# mcu.net
KiCad netlist of a schematic drawn in Altium Designer
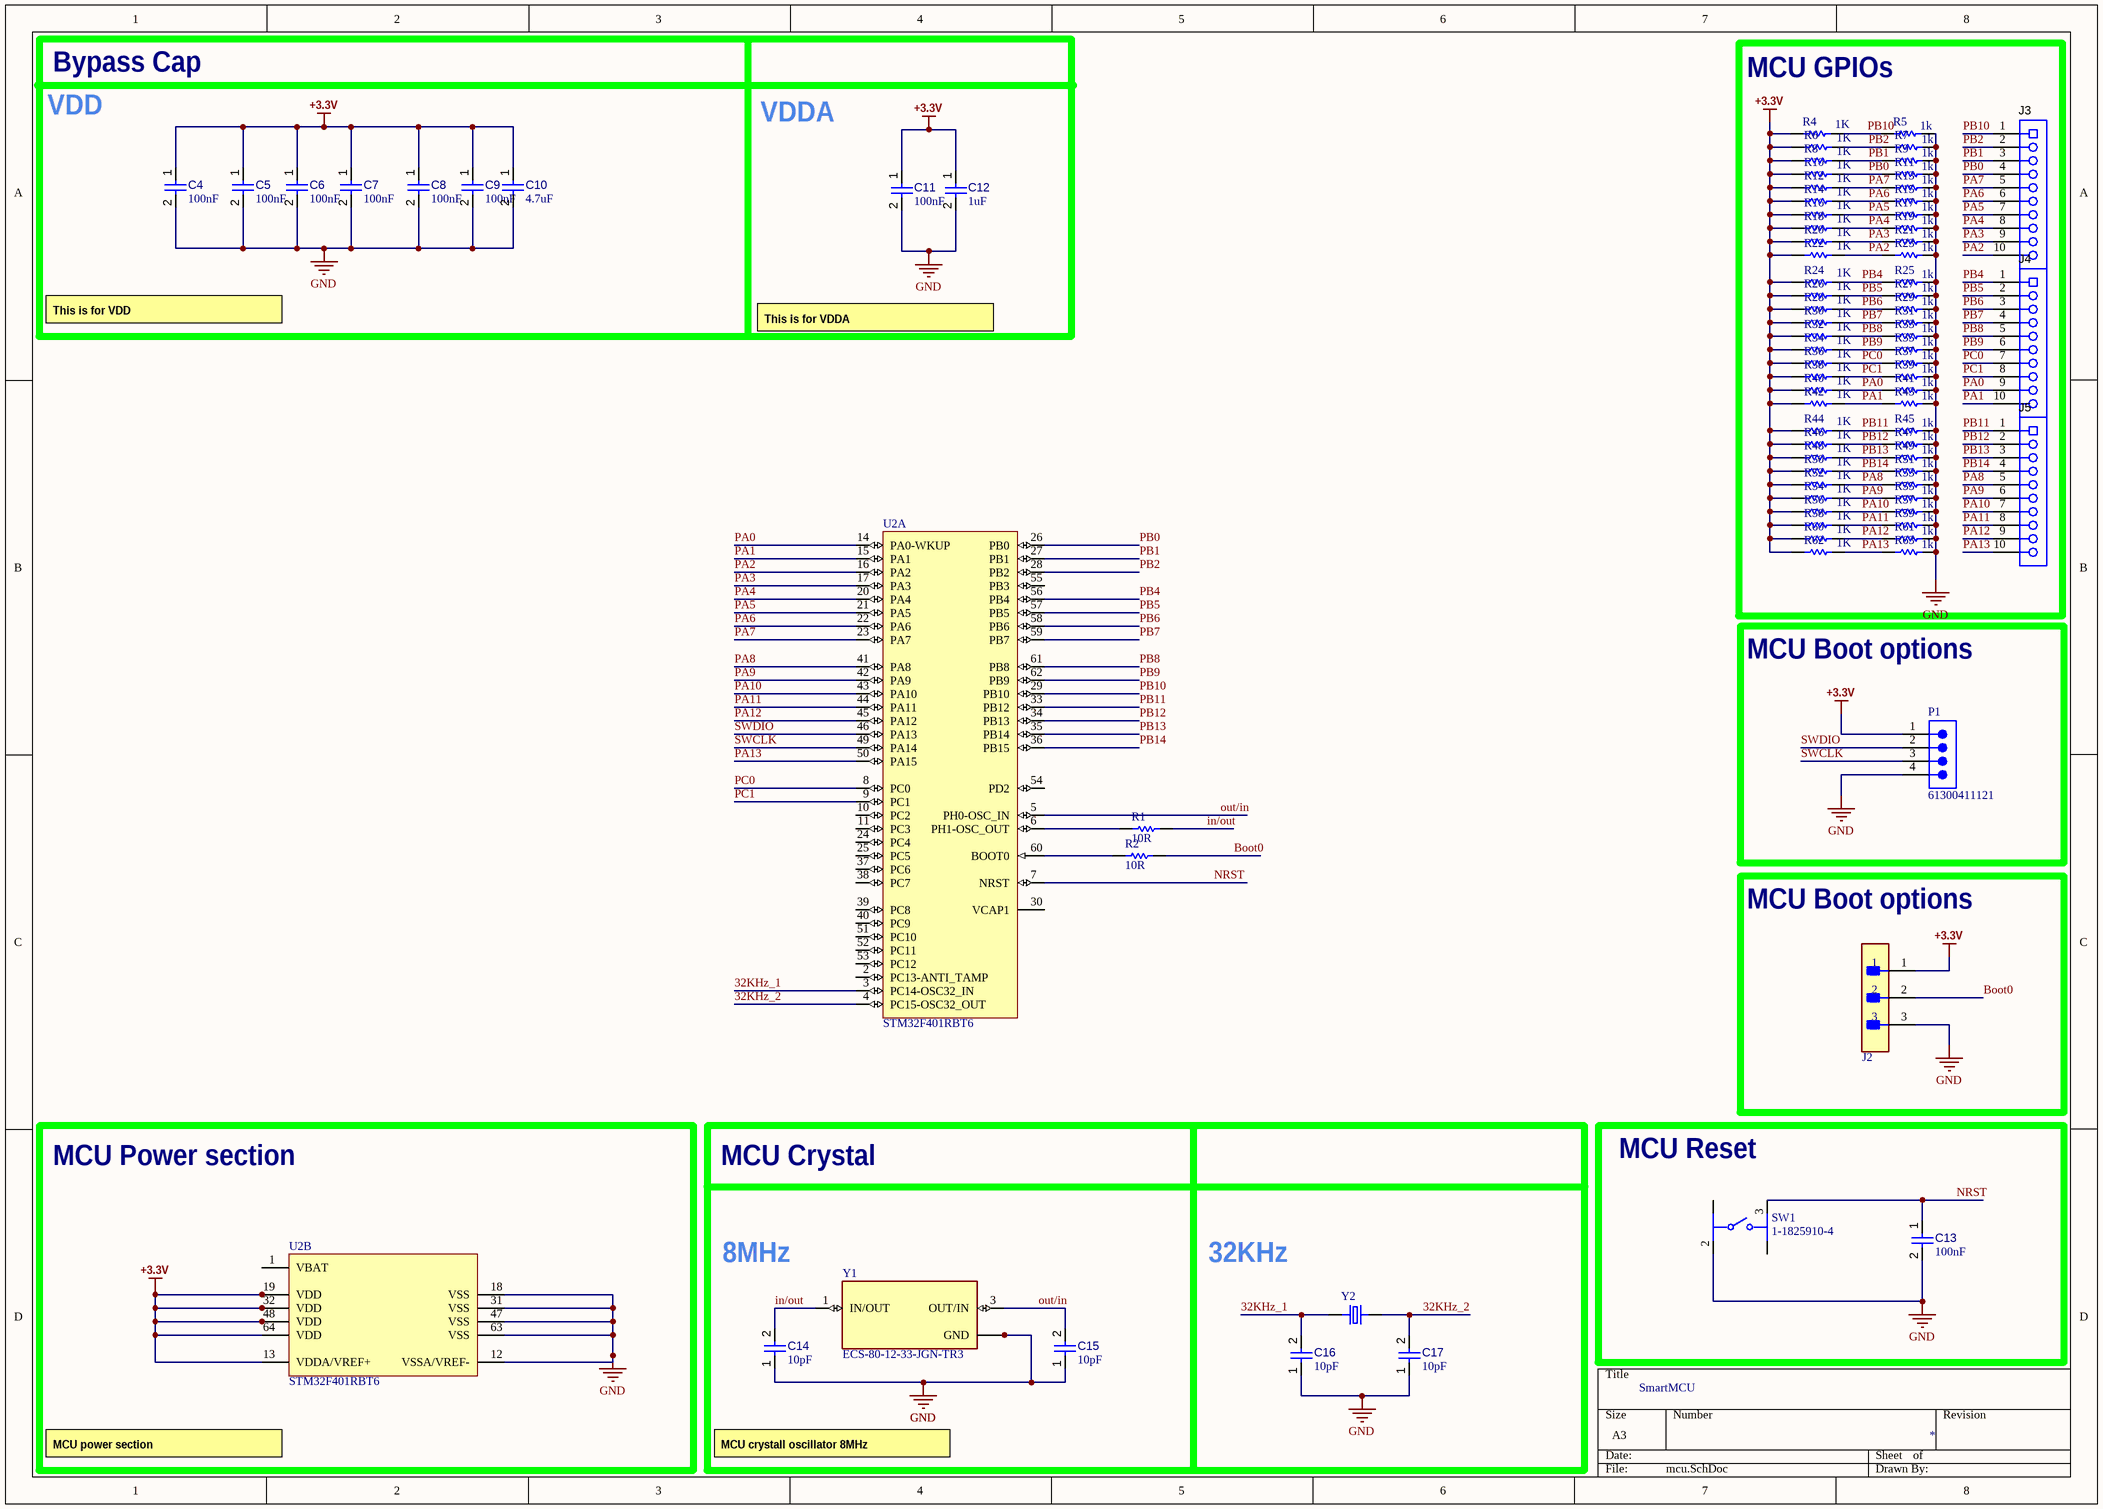
[diagram p0: mcu.SchDoc]

(export (version "E")
  (design (tool "Eeschema 10.0.6"))
  (components
    (comp (ref "C4")
      (value "100nF")
      (footprint "CAPC0603(1608)100_L")
      (description "Chip Capacitor, 4.7µF +/-20%, 10V, 0603, Thickness 1 mm")
      (fields (field (name "TOLERANCE") "10%") (field (name "Comment") "Capacitor 4.7µF +/-20% 10V 0603"))
      (libsource (lib "Altium Cloud") (part "CAP-NP-2"))
    )
    (comp (ref "C5")
      (value "100nF")
      (footprint "CAPC0603(1608)100_L")
      (description "Chip Capacitor, 4.7µF +/-20%, 10V, 0603, Thickness 1 mm")
      (fields (field (name "TOLERANCE") "10%") (field (name "Comment") "Capacitor 4.7µF +/-20% 10V 0603"))
      (libsource (lib "Altium Cloud") (part "CAP-NP-2"))
    )
    (comp (ref "C6")
      (value "100nF")
      (footprint "CAPC0603(1608)100_L")
      (description "Chip Capacitor, 4.7µF +/-20%, 10V, 0603, Thickness 1 mm")
      (fields (field (name "TOLERANCE") "10%") (field (name "Comment") "Capacitor 4.7µF +/-20% 10V 0603"))
      (libsource (lib "Altium Cloud") (part "CAP-NP-2"))
    )
    (comp (ref "C7")
      (value "100nF")
      (footprint "CAPC0603(1608)100_L")
      (description "Chip Capacitor, 4.7µF +/-20%, 10V, 0603, Thickness 1 mm")
      (fields (field (name "TOLERANCE") "10%") (field (name "Comment") "Capacitor 4.7µF +/-20% 10V 0603"))
      (libsource (lib "Altium Cloud") (part "CAP-NP-2"))
    )
    (comp (ref "C8")
      (value "100nF")
      (footprint "CAPC0603(1608)100_L")
      (description "Chip Capacitor, 4.7µF +/-20%, 10V, 0603, Thickness 1 mm")
      (fields (field (name "TOLERANCE") "10%") (field (name "Comment") "Capacitor 4.7µF +/-20% 10V 0603"))
      (libsource (lib "Altium Cloud") (part "CAP-NP-2"))
    )
    (comp (ref "C9")
      (value "100nF")
      (footprint "CAPC0603(1608)100_L")
      (description "Chip Capacitor, 4.7µF +/-20%, 10V, 0603, Thickness 1 mm")
      (fields (field (name "TOLERANCE") "10%") (field (name "Comment") "Capacitor 4.7µF +/-20% 10V 0603"))
      (libsource (lib "Altium Cloud") (part "CAP-NP-2"))
    )
    (comp (ref "C10")
      (value "4.7uF")
      (footprint "CAPC0603(1608)100_L")
      (description "Chip Capacitor, 4.7µF +/-20%, 10V, 0603, Thickness 1 mm")
      (fields (field (name "TOLERANCE") "10%") (field (name "Comment") "Capacitor 4.7µF +/-20% 10V 0603"))
      (libsource (lib "Altium Cloud") (part "CAP-NP-2"))
    )
    (comp (ref "C11")
      (value "100nF")
      (footprint "CAPC0603(1608)100_L")
      (description "Chip Capacitor, 4.7µF +/-20%, 10V, 0603, Thickness 1 mm")
      (fields (field (name "TOLERANCE") "10%") (field (name "Comment") "Capacitor 4.7µF +/-20% 10V 0603"))
      (libsource (lib "Altium Cloud") (part "CAP-NP-2"))
    )
    (comp (ref "C12")
      (value "1uF")
      (footprint "CAPC0603(1608)100_L")
      (description "Chip Capacitor, 4.7µF +/-20%, 10V, 0603, Thickness 1 mm")
      (fields (field (name "TOLERANCE") "10%") (field (name "Comment") "Capacitor 4.7µF +/-20% 10V 0603"))
      (libsource (lib "Altium Cloud") (part "CAP-NP-2"))
    )
    (comp (ref "C13")
      (value "100nF")
      (footprint "CAPC0603(1608)100_L")
      (description "Chip Capacitor, 4.7µF +/-20%, 10V, 0603, Thickness 1 mm")
      (fields (field (name "TOLERANCE") "10%") (field (name "Comment") "Capacitor 4.7µF +/-20% 10V 0603"))
      (libsource (lib "Altium Cloud") (part "CAP-NP-2"))
    )
    (comp (ref "C14")
      (value "10pF")
      (footprint "CAPC0402(1005)33_L")
      (description "Chip Capacitor, 12pF +/-10%, 50V, 0402, Thickness 0.33 mm")
      (fields (field (name "TOLERANCE") "20%") (field (name "Comment") "Capacitor 12pF +/-10% 50V 0402"))
      (libsource (lib "Altium Cloud") (part "CAP-NP-2"))
    )
    (comp (ref "C15")
      (value "10pF")
      (footprint "CAPC0402(1005)33_L")
      (description "Chip Capacitor, 12pF +/-10%, 50V, 0402, Thickness 0.33 mm")
      (fields (field (name "TOLERANCE") "20%") (field (name "Comment") "Capacitor 12pF +/-10% 50V 0402"))
      (libsource (lib "Altium Cloud") (part "CAP-NP-2"))
    )
    (comp (ref "C16")
      (value "10pF")
      (footprint "CAPC0402(1005)33_L")
      (description "Chip Capacitor, 12pF +/-10%, 50V, 0402, Thickness 0.33 mm")
      (fields (field (name "TOLERANCE") "20%") (field (name "Comment") "Capacitor 12pF +/-10% 50V 0402"))
      (libsource (lib "Altium Cloud") (part "CAP-NP-2"))
    )
    (comp (ref "C17")
      (value "10pF")
      (footprint "CAPC0402(1005)33_L")
      (description "Chip Capacitor, 12pF +/-10%, 50V, 0402, Thickness 0.33 mm")
      (fields (field (name "TOLERANCE") "20%") (field (name "Comment") "Capacitor 12pF +/-10% 50V 0402"))
      (libsource (lib "Altium Cloud") (part "CAP-NP-2"))
    )
    (comp (ref "J2")
      (value "951103-8622-AR")
      (footprint "FP-951103-8622-AR-MFG")
      (description "CONN HEADER VERT 3POS 2MM")
      (fields
        (field (name "OCTOPART") "https://octopart.com/951103-8622-ar-3m-14400669")
        (field (name "MANUFACTURER") "3M")
      )
      (libsource (lib "Altium Content Vault") (part "0d3f023dd272f625e17a2be33dea85f"))
    )
    (comp (ref "J3")
      (value "5-534237-8")
      (footprint "TECO-5-534237-8_V")
      (fields (field (name "MANUFACTURER") "TE Connectivity"))
      (libsource (lib "Altium Cloud") (part "CN-1P-F-R10"))
    )
    (comp (ref "J4")
      (value "5-534237-8")
      (footprint "TECO-5-534237-8_V")
      (fields (field (name "MANUFACTURER") "TE Connectivity"))
      (libsource (lib "Altium Cloud") (part "CN-1P-F-R10"))
    )
    (comp (ref "J5")
      (value "5-534237-8")
      (footprint "TECO-5-534237-8_V")
      (fields (field (name "MANUFACTURER") "TE Connectivity"))
      (libsource (lib "Altium Cloud") (part "CN-1P-F-R10"))
    )
    (comp (ref "P1")
      (value "61300411121")
      (footprint "61300411121")
      (libsource (lib "Altium Content Vault") (part "Header_Male_1R_04P"))
    )
    (comp (ref "R1")
      (value "10R")
      (footprint "RESC1608X55X25ML10T15")
      (description "Chip Resistor, 0 Ohm, 0.1 W, -55 to 155 degC, 0603 (1608 Metric)")
      (fields (field (name "POWER") "100mW") (field (name "TOLERANCE") "5%"))
      (libsource (lib "Altium Cloud") (part "RES-2"))
    )
    (comp (ref "R2")
      (value "10R")
      (footprint "RESC1608X55X25ML10T15")
      (description "Chip Resistor, 0 Ohm, 0.1 W, -55 to 155 degC, 0603 (1608 Metric)")
      (fields (field (name "POWER") "100mW") (field (name "TOLERANCE") "5%"))
      (libsource (lib "Altium Cloud") (part "RES-2"))
    )
    (comp (ref "R4")
      (value "1K")
      (footprint "RESC1608X55X25ML10T15")
      (description "Chip Resistor, 0 Ohm, 0.1 W, -55 to 155 degC, 0603 (1608 Metric)")
      (fields (field (name "POWER") "100mW") (field (name "TOLERANCE") "5%"))
      (libsource (lib "Altium Cloud") (part "RES-2"))
    )
    (comp (ref "R5")
      (value "1k")
      (footprint "RESC1608X55X25ML10T15")
      (description "Chip Resistor, 0 Ohm, 0.1 W, -55 to 155 degC, 0603 (1608 Metric)")
      (fields (field (name "POWER") "100mW") (field (name "TOLERANCE") "5%"))
      (libsource (lib "Altium Cloud") (part "RES-2"))
    )
    (comp (ref "R6")
      (value "1K")
      (footprint "RESC1608X55X25ML10T15")
      (description "Chip Resistor, 0 Ohm, 0.1 W, -55 to 155 degC, 0603 (1608 Metric)")
      (fields (field (name "POWER") "100mW") (field (name "TOLERANCE") "5%"))
      (libsource (lib "Altium Cloud") (part "RES-2"))
    )
    (comp (ref "R7")
      (value "1k")
      (footprint "RESC1608X55X25ML10T15")
      (description "Chip Resistor, 0 Ohm, 0.1 W, -55 to 155 degC, 0603 (1608 Metric)")
      (fields (field (name "POWER") "100mW") (field (name "TOLERANCE") "5%"))
      (libsource (lib "Altium Cloud") (part "RES-2"))
    )
    (comp (ref "R8")
      (value "1K")
      (footprint "RESC1608X55X25ML10T15")
      (description "Chip Resistor, 0 Ohm, 0.1 W, -55 to 155 degC, 0603 (1608 Metric)")
      (fields (field (name "POWER") "100mW") (field (name "TOLERANCE") "5%"))
      (libsource (lib "Altium Cloud") (part "RES-2"))
    )
    (comp (ref "R9")
      (value "1k")
      (footprint "RESC1608X55X25ML10T15")
      (description "Chip Resistor, 0 Ohm, 0.1 W, -55 to 155 degC, 0603 (1608 Metric)")
      (fields (field (name "POWER") "100mW") (field (name "TOLERANCE") "5%"))
      (libsource (lib "Altium Cloud") (part "RES-2"))
    )
    (comp (ref "R10")
      (value "1K")
      (footprint "RESC1608X55X25ML10T15")
      (description "Chip Resistor, 0 Ohm, 0.1 W, -55 to 155 degC, 0603 (1608 Metric)")
      (fields (field (name "POWER") "100mW") (field (name "TOLERANCE") "5%"))
      (libsource (lib "Altium Cloud") (part "RES-2"))
    )
    (comp (ref "R11")
      (value "1k")
      (footprint "RESC1608X55X25ML10T15")
      (description "Chip Resistor, 0 Ohm, 0.1 W, -55 to 155 degC, 0603 (1608 Metric)")
      (fields (field (name "POWER") "100mW") (field (name "TOLERANCE") "5%"))
      (libsource (lib "Altium Cloud") (part "RES-2"))
    )
    (comp (ref "R12")
      (value "1K")
      (footprint "RESC1608X55X25ML10T15")
      (description "Chip Resistor, 0 Ohm, 0.1 W, -55 to 155 degC, 0603 (1608 Metric)")
      (fields (field (name "POWER") "100mW") (field (name "TOLERANCE") "5%"))
      (libsource (lib "Altium Cloud") (part "RES-2"))
    )
    (comp (ref "R13")
      (value "1k")
      (footprint "RESC1608X55X25ML10T15")
      (description "Chip Resistor, 0 Ohm, 0.1 W, -55 to 155 degC, 0603 (1608 Metric)")
      (fields (field (name "POWER") "100mW") (field (name "TOLERANCE") "5%"))
      (libsource (lib "Altium Cloud") (part "RES-2"))
    )
    (comp (ref "R14")
      (value "1K")
      (footprint "RESC1608X55X25ML10T15")
      (description "Chip Resistor, 0 Ohm, 0.1 W, -55 to 155 degC, 0603 (1608 Metric)")
      (fields (field (name "POWER") "100mW") (field (name "TOLERANCE") "5%"))
      (libsource (lib "Altium Cloud") (part "RES-2"))
    )
    (comp (ref "R15")
      (value "1k")
      (footprint "RESC1608X55X25ML10T15")
      (description "Chip Resistor, 0 Ohm, 0.1 W, -55 to 155 degC, 0603 (1608 Metric)")
      (fields (field (name "POWER") "100mW") (field (name "TOLERANCE") "5%"))
      (libsource (lib "Altium Cloud") (part "RES-2"))
    )
    (comp (ref "R16")
      (value "1K")
      (footprint "RESC1608X55X25ML10T15")
      (description "Chip Resistor, 0 Ohm, 0.1 W, -55 to 155 degC, 0603 (1608 Metric)")
      (fields (field (name "POWER") "100mW") (field (name "TOLERANCE") "5%"))
      (libsource (lib "Altium Cloud") (part "RES-2"))
    )
    (comp (ref "R17")
      (value "1k")
      (footprint "RESC1608X55X25ML10T15")
      (description "Chip Resistor, 0 Ohm, 0.1 W, -55 to 155 degC, 0603 (1608 Metric)")
      (fields (field (name "POWER") "100mW") (field (name "TOLERANCE") "5%"))
      (libsource (lib "Altium Cloud") (part "RES-2"))
    )
    (comp (ref "R18")
      (value "1K")
      (footprint "RESC1608X55X25ML10T15")
      (description "Chip Resistor, 0 Ohm, 0.1 W, -55 to 155 degC, 0603 (1608 Metric)")
      (fields (field (name "POWER") "100mW") (field (name "TOLERANCE") "5%"))
      (libsource (lib "Altium Cloud") (part "RES-2"))
    )
    (comp (ref "R19")
      (value "1k")
      (footprint "RESC1608X55X25ML10T15")
      (description "Chip Resistor, 0 Ohm, 0.1 W, -55 to 155 degC, 0603 (1608 Metric)")
      (fields (field (name "POWER") "100mW") (field (name "TOLERANCE") "5%"))
      (libsource (lib "Altium Cloud") (part "RES-2"))
    )
    (comp (ref "R20")
      (value "1K")
      (footprint "RESC1608X55X25ML10T15")
      (description "Chip Resistor, 0 Ohm, 0.1 W, -55 to 155 degC, 0603 (1608 Metric)")
      (fields (field (name "POWER") "100mW") (field (name "TOLERANCE") "5%"))
      (libsource (lib "Altium Cloud") (part "RES-2"))
    )
    (comp (ref "R21")
      (value "1k")
      (footprint "RESC1608X55X25ML10T15")
      (description "Chip Resistor, 0 Ohm, 0.1 W, -55 to 155 degC, 0603 (1608 Metric)")
      (fields (field (name "POWER") "100mW") (field (name "TOLERANCE") "5%"))
      (libsource (lib "Altium Cloud") (part "RES-2"))
    )
    (comp (ref "R22")
      (value "1K")
      (footprint "RESC1608X55X25ML10T15")
      (description "Chip Resistor, 0 Ohm, 0.1 W, -55 to 155 degC, 0603 (1608 Metric)")
      (fields (field (name "POWER") "100mW") (field (name "TOLERANCE") "5%"))
      (libsource (lib "Altium Cloud") (part "RES-2"))
    )
    (comp (ref "R23")
      (value "1k")
      (footprint "RESC1608X55X25ML10T15")
      (description "Chip Resistor, 0 Ohm, 0.1 W, -55 to 155 degC, 0603 (1608 Metric)")
      (fields (field (name "POWER") "100mW") (field (name "TOLERANCE") "5%"))
      (libsource (lib "Altium Cloud") (part "RES-2"))
    )
    (comp (ref "R24")
      (value "1K")
      (footprint "RESC1608X55X25ML10T15")
      (description "Chip Resistor, 0 Ohm, 0.1 W, -55 to 155 degC, 0603 (1608 Metric)")
      (fields (field (name "POWER") "100mW") (field (name "TOLERANCE") "5%"))
      (libsource (lib "Altium Cloud") (part "RES-2"))
    )
    (comp (ref "R25")
      (value "1k")
      (footprint "RESC1608X55X25ML10T15")
      (description "Chip Resistor, 0 Ohm, 0.1 W, -55 to 155 degC, 0603 (1608 Metric)")
      (fields (field (name "POWER") "100mW") (field (name "TOLERANCE") "5%"))
      (libsource (lib "Altium Cloud") (part "RES-2"))
    )
    (comp (ref "R26")
      (value "1K")
      (footprint "RESC1608X55X25ML10T15")
      (description "Chip Resistor, 0 Ohm, 0.1 W, -55 to 155 degC, 0603 (1608 Metric)")
      (fields (field (name "POWER") "100mW") (field (name "TOLERANCE") "5%"))
      (libsource (lib "Altium Cloud") (part "RES-2"))
    )
    (comp (ref "R27")
      (value "1k")
      (footprint "RESC1608X55X25ML10T15")
      (description "Chip Resistor, 0 Ohm, 0.1 W, -55 to 155 degC, 0603 (1608 Metric)")
      (fields (field (name "POWER") "100mW") (field (name "TOLERANCE") "5%"))
      (libsource (lib "Altium Cloud") (part "RES-2"))
    )
    (comp (ref "R28")
      (value "1K")
      (footprint "RESC1608X55X25ML10T15")
      (description "Chip Resistor, 0 Ohm, 0.1 W, -55 to 155 degC, 0603 (1608 Metric)")
      (fields (field (name "POWER") "100mW") (field (name "TOLERANCE") "5%"))
      (libsource (lib "Altium Cloud") (part "RES-2"))
    )
    (comp (ref "R29")
      (value "1k")
      (footprint "RESC1608X55X25ML10T15")
      (description "Chip Resistor, 0 Ohm, 0.1 W, -55 to 155 degC, 0603 (1608 Metric)")
      (fields (field (name "POWER") "100mW") (field (name "TOLERANCE") "5%"))
      (libsource (lib "Altium Cloud") (part "RES-2"))
    )
    (comp (ref "R30")
      (value "1K")
      (footprint "RESC1608X55X25ML10T15")
      (description "Chip Resistor, 0 Ohm, 0.1 W, -55 to 155 degC, 0603 (1608 Metric)")
      (fields (field (name "POWER") "100mW") (field (name "TOLERANCE") "5%"))
      (libsource (lib "Altium Cloud") (part "RES-2"))
    )
    (comp (ref "R31")
      (value "1k")
      (footprint "RESC1608X55X25ML10T15")
      (description "Chip Resistor, 0 Ohm, 0.1 W, -55 to 155 degC, 0603 (1608 Metric)")
      (fields (field (name "POWER") "100mW") (field (name "TOLERANCE") "5%"))
      (libsource (lib "Altium Cloud") (part "RES-2"))
    )
    (comp (ref "R32")
      (value "1K")
      (footprint "RESC1608X55X25ML10T15")
      (description "Chip Resistor, 0 Ohm, 0.1 W, -55 to 155 degC, 0603 (1608 Metric)")
      (fields (field (name "POWER") "100mW") (field (name "TOLERANCE") "5%"))
      (libsource (lib "Altium Cloud") (part "RES-2"))
    )
    (comp (ref "R33")
      (value "1k")
      (footprint "RESC1608X55X25ML10T15")
      (description "Chip Resistor, 0 Ohm, 0.1 W, -55 to 155 degC, 0603 (1608 Metric)")
      (fields (field (name "POWER") "100mW") (field (name "TOLERANCE") "5%"))
      (libsource (lib "Altium Cloud") (part "RES-2"))
    )
    (comp (ref "R34")
      (value "1K")
      (footprint "RESC1608X55X25ML10T15")
      (description "Chip Resistor, 0 Ohm, 0.1 W, -55 to 155 degC, 0603 (1608 Metric)")
      (fields (field (name "POWER") "100mW") (field (name "TOLERANCE") "5%"))
      (libsource (lib "Altium Cloud") (part "RES-2"))
    )
    (comp (ref "R35")
      (value "1k")
      (footprint "RESC1608X55X25ML10T15")
      (description "Chip Resistor, 0 Ohm, 0.1 W, -55 to 155 degC, 0603 (1608 Metric)")
      (fields (field (name "POWER") "100mW") (field (name "TOLERANCE") "5%"))
      (libsource (lib "Altium Cloud") (part "RES-2"))
    )
    (comp (ref "R36")
      (value "1K")
      (footprint "RESC1608X55X25ML10T15")
      (description "Chip Resistor, 0 Ohm, 0.1 W, -55 to 155 degC, 0603 (1608 Metric)")
      (fields (field (name "POWER") "100mW") (field (name "TOLERANCE") "5%"))
      (libsource (lib "Altium Cloud") (part "RES-2"))
    )
    (comp (ref "R37")
      (value "1k")
      (footprint "RESC1608X55X25ML10T15")
      (description "Chip Resistor, 0 Ohm, 0.1 W, -55 to 155 degC, 0603 (1608 Metric)")
      (fields (field (name "POWER") "100mW") (field (name "TOLERANCE") "5%"))
      (libsource (lib "Altium Cloud") (part "RES-2"))
    )
    (comp (ref "R38")
      (value "1K")
      (footprint "RESC1608X55X25ML10T15")
      (description "Chip Resistor, 0 Ohm, 0.1 W, -55 to 155 degC, 0603 (1608 Metric)")
      (fields (field (name "POWER") "100mW") (field (name "TOLERANCE") "5%"))
      (libsource (lib "Altium Cloud") (part "RES-2"))
    )
    (comp (ref "R39")
      (value "1k")
      (footprint "RESC1608X55X25ML10T15")
      (description "Chip Resistor, 0 Ohm, 0.1 W, -55 to 155 degC, 0603 (1608 Metric)")
      (fields (field (name "POWER") "100mW") (field (name "TOLERANCE") "5%"))
      (libsource (lib "Altium Cloud") (part "RES-2"))
    )
    (comp (ref "R40")
      (value "1K")
      (footprint "RESC1608X55X25ML10T15")
      (description "Chip Resistor, 0 Ohm, 0.1 W, -55 to 155 degC, 0603 (1608 Metric)")
      (fields (field (name "POWER") "100mW") (field (name "TOLERANCE") "5%"))
      (libsource (lib "Altium Cloud") (part "RES-2"))
    )
    (comp (ref "R41")
      (value "1k")
      (footprint "RESC1608X55X25ML10T15")
      (description "Chip Resistor, 0 Ohm, 0.1 W, -55 to 155 degC, 0603 (1608 Metric)")
      (fields (field (name "POWER") "100mW") (field (name "TOLERANCE") "5%"))
      (libsource (lib "Altium Cloud") (part "RES-2"))
    )
    (comp (ref "R42")
      (value "1K")
      (footprint "RESC1608X55X25ML10T15")
      (description "Chip Resistor, 0 Ohm, 0.1 W, -55 to 155 degC, 0603 (1608 Metric)")
      (fields (field (name "POWER") "100mW") (field (name "TOLERANCE") "5%"))
      (libsource (lib "Altium Cloud") (part "RES-2"))
    )
    (comp (ref "R43")
      (value "1k")
      (footprint "RESC1608X55X25ML10T15")
      (description "Chip Resistor, 0 Ohm, 0.1 W, -55 to 155 degC, 0603 (1608 Metric)")
      (fields (field (name "POWER") "100mW") (field (name "TOLERANCE") "5%"))
      (libsource (lib "Altium Cloud") (part "RES-2"))
    )
    (comp (ref "R44")
      (value "1K")
      (footprint "RESC1608X55X25ML10T15")
      (description "Chip Resistor, 0 Ohm, 0.1 W, -55 to 155 degC, 0603 (1608 Metric)")
      (fields (field (name "POWER") "100mW") (field (name "TOLERANCE") "5%"))
      (libsource (lib "Altium Cloud") (part "RES-2"))
    )
    (comp (ref "R45")
      (value "1k")
      (footprint "RESC1608X55X25ML10T15")
      (description "Chip Resistor, 0 Ohm, 0.1 W, -55 to 155 degC, 0603 (1608 Metric)")
      (fields (field (name "POWER") "100mW") (field (name "TOLERANCE") "5%"))
      (libsource (lib "Altium Cloud") (part "RES-2"))
    )
    (comp (ref "R46")
      (value "1K")
      (footprint "RESC1608X55X25ML10T15")
      (description "Chip Resistor, 0 Ohm, 0.1 W, -55 to 155 degC, 0603 (1608 Metric)")
      (fields (field (name "POWER") "100mW") (field (name "TOLERANCE") "5%"))
      (libsource (lib "Altium Cloud") (part "RES-2"))
    )
    (comp (ref "R47")
      (value "1k")
      (footprint "RESC1608X55X25ML10T15")
      (description "Chip Resistor, 0 Ohm, 0.1 W, -55 to 155 degC, 0603 (1608 Metric)")
      (fields (field (name "POWER") "100mW") (field (name "TOLERANCE") "5%"))
      (libsource (lib "Altium Cloud") (part "RES-2"))
    )
    (comp (ref "R48")
      (value "1K")
      (footprint "RESC1608X55X25ML10T15")
      (description "Chip Resistor, 0 Ohm, 0.1 W, -55 to 155 degC, 0603 (1608 Metric)")
      (fields (field (name "POWER") "100mW") (field (name "TOLERANCE") "5%"))
      (libsource (lib "Altium Cloud") (part "RES-2"))
    )
    (comp (ref "R49")
      (value "1k")
      (footprint "RESC1608X55X25ML10T15")
      (description "Chip Resistor, 0 Ohm, 0.1 W, -55 to 155 degC, 0603 (1608 Metric)")
      (fields (field (name "POWER") "100mW") (field (name "TOLERANCE") "5%"))
      (libsource (lib "Altium Cloud") (part "RES-2"))
    )
    (comp (ref "R50")
      (value "1K")
      (footprint "RESC1608X55X25ML10T15")
      (description "Chip Resistor, 0 Ohm, 0.1 W, -55 to 155 degC, 0603 (1608 Metric)")
      (fields (field (name "POWER") "100mW") (field (name "TOLERANCE") "5%"))
      (libsource (lib "Altium Cloud") (part "RES-2"))
    )
    (comp (ref "R51")
      (value "1k")
      (footprint "RESC1608X55X25ML10T15")
      (description "Chip Resistor, 0 Ohm, 0.1 W, -55 to 155 degC, 0603 (1608 Metric)")
      (fields (field (name "POWER") "100mW") (field (name "TOLERANCE") "5%"))
      (libsource (lib "Altium Cloud") (part "RES-2"))
    )
    (comp (ref "R52")
      (value "1K")
      (footprint "RESC1608X55X25ML10T15")
      (description "Chip Resistor, 0 Ohm, 0.1 W, -55 to 155 degC, 0603 (1608 Metric)")
      (fields (field (name "POWER") "100mW") (field (name "TOLERANCE") "5%"))
      (libsource (lib "Altium Cloud") (part "RES-2"))
    )
    (comp (ref "R53")
      (value "1k")
      (footprint "RESC1608X55X25ML10T15")
      (description "Chip Resistor, 0 Ohm, 0.1 W, -55 to 155 degC, 0603 (1608 Metric)")
      (fields (field (name "POWER") "100mW") (field (name "TOLERANCE") "5%"))
      (libsource (lib "Altium Cloud") (part "RES-2"))
    )
    (comp (ref "R54")
      (value "1K")
      (footprint "RESC1608X55X25ML10T15")
      (description "Chip Resistor, 0 Ohm, 0.1 W, -55 to 155 degC, 0603 (1608 Metric)")
      (fields (field (name "POWER") "100mW") (field (name "TOLERANCE") "5%"))
      (libsource (lib "Altium Cloud") (part "RES-2"))
    )
    (comp (ref "R55")
      (value "1k")
      (footprint "RESC1608X55X25ML10T15")
      (description "Chip Resistor, 0 Ohm, 0.1 W, -55 to 155 degC, 0603 (1608 Metric)")
      (fields (field (name "POWER") "100mW") (field (name "TOLERANCE") "5%"))
      (libsource (lib "Altium Cloud") (part "RES-2"))
    )
    (comp (ref "R56")
      (value "1K")
      (footprint "RESC1608X55X25ML10T15")
      (description "Chip Resistor, 0 Ohm, 0.1 W, -55 to 155 degC, 0603 (1608 Metric)")
      (fields (field (name "POWER") "100mW") (field (name "TOLERANCE") "5%"))
      (libsource (lib "Altium Cloud") (part "RES-2"))
    )
    (comp (ref "R57")
      (value "1k")
      (footprint "RESC1608X55X25ML10T15")
      (description "Chip Resistor, 0 Ohm, 0.1 W, -55 to 155 degC, 0603 (1608 Metric)")
      (fields (field (name "POWER") "100mW") (field (name "TOLERANCE") "5%"))
      (libsource (lib "Altium Cloud") (part "RES-2"))
    )
    (comp (ref "R58")
      (value "1K")
      (footprint "RESC1608X55X25ML10T15")
      (description "Chip Resistor, 0 Ohm, 0.1 W, -55 to 155 degC, 0603 (1608 Metric)")
      (fields (field (name "POWER") "100mW") (field (name "TOLERANCE") "5%"))
      (libsource (lib "Altium Cloud") (part "RES-2"))
    )
    (comp (ref "R59")
      (value "1k")
      (footprint "RESC1608X55X25ML10T15")
      (description "Chip Resistor, 0 Ohm, 0.1 W, -55 to 155 degC, 0603 (1608 Metric)")
      (fields (field (name "POWER") "100mW") (field (name "TOLERANCE") "5%"))
      (libsource (lib "Altium Cloud") (part "RES-2"))
    )
    (comp (ref "R60")
      (value "1K")
      (footprint "RESC1608X55X25ML10T15")
      (description "Chip Resistor, 0 Ohm, 0.1 W, -55 to 155 degC, 0603 (1608 Metric)")
      (fields (field (name "POWER") "100mW") (field (name "TOLERANCE") "5%"))
      (libsource (lib "Altium Cloud") (part "RES-2"))
    )
    (comp (ref "R61")
      (value "1k")
      (footprint "RESC1608X55X25ML10T15")
      (description "Chip Resistor, 0 Ohm, 0.1 W, -55 to 155 degC, 0603 (1608 Metric)")
      (fields (field (name "POWER") "100mW") (field (name "TOLERANCE") "5%"))
      (libsource (lib "Altium Cloud") (part "RES-2"))
    )
    (comp (ref "R62")
      (value "1K")
      (footprint "RESC1608X55X25ML10T15")
      (description "Chip Resistor, 0 Ohm, 0.1 W, -55 to 155 degC, 0603 (1608 Metric)")
      (fields (field (name "POWER") "100mW") (field (name "TOLERANCE") "5%"))
      (libsource (lib "Altium Cloud") (part "RES-2"))
    )
    (comp (ref "R63")
      (value "1k")
      (footprint "RESC1608X55X25ML10T15")
      (description "Chip Resistor, 0 Ohm, 0.1 W, -55 to 155 degC, 0603 (1608 Metric)")
      (fields (field (name "POWER") "100mW") (field (name "TOLERANCE") "5%"))
      (libsource (lib "Altium Cloud") (part "RES-2"))
    )
    (comp (ref "SW1")
      (value "1-1825910-4")
      (footprint "FP-1-1825910-4-MFG")
      (description "SWITCH TACTILE SPST-NO 0.05A 24V")
      (fields
        (field (name "OCTOPART") "https://octopart.com/1-1825910-4-te+connectivity-42270468")
        (field (name "MANUFACTURER") "TE Connectivity")
      )
      (libsource (lib "Altium Content Vault") (part "b8895f3f4cefb76e1819d2863dba89b"))
    )
    (comp (ref "U2")
      (value "STM32F401RBT6")
      (footprint "STM-LQFP64_M")
      (description "ARM Cortex -M4 32b MCU+FPU, 256 KB Flash, 64 KB RAM, -40 to 85 degC, 64-Pin LQFP, RoHS, Tray")
      (fields (field (name "POWER") "313mW") (field (name "MANUFACTURER") "STMicroelectronics"))
      (libsource (lib "Altium Cloud") (part "MC-ARM-STM32F401-SQ64"))
    )
    (comp (ref "Y1")
      (value "ECS-80-12-33-JGN-TR3")
      (footprint "XTAL_ECS-240-8-33-AGN-TR")
      (description "Crystal 8MHz Â±20ppm (Tol) Â±30ppm (Stability) 12pF FUND 400Ohm 4-Pin Mini-CSMD T/R")
      (fields (field (name "MF") "ECS Inc."))
      (libsource (lib "ECS-80-12-33-JGN-TR3") (part "ECS-80-12-33-JGN-TR3"))
    )
    (comp (ref "Y2")
      (value "ECS-.320-12.5-13")
      (footprint "XTAL_ECS-.655-12.5-13X")
      (description "Crystal  Cylindrical Can, Radial")
      (libsource (lib "ECS-.320-12.5-13") (part "ECS-.320-12.5-13"))
    )
  )
  (nets
    (net (code "1") (name "+3.3V") (class "Default")
      (node (ref "C10") (pin "1") (pinfunction "1_1") (pintype "passive"))
      (node (ref "C11") (pin "1") (pinfunction "1_1") (pintype "passive"))
      (node (ref "C12") (pin "1") (pinfunction "1_1") (pintype "passive"))
      (node (ref "C4") (pin "1") (pinfunction "1_1") (pintype "passive"))
      (node (ref "C5") (pin "1") (pinfunction "1_1") (pintype "passive"))
      (node (ref "C6") (pin "1") (pinfunction "1_1") (pintype "passive"))
      (node (ref "C7") (pin "1") (pinfunction "1_1") (pintype "passive"))
      (node (ref "C8") (pin "1") (pinfunction "1_1") (pintype "passive"))
      (node (ref "C9") (pin "1") (pinfunction "1_1") (pintype "passive"))
      (node (ref "J2") (pin "1") (pinfunction "1_1") (pintype "passive"))
      (node (ref "P1") (pin "1") (pinfunction "1_1") (pintype "passive"))
      (node (ref "R10") (pin "1") (pinfunction "1_1") (pintype "passive"))
      (node (ref "R12") (pin "1") (pinfunction "1_1") (pintype "passive"))
      (node (ref "R14") (pin "1") (pinfunction "1_1") (pintype "passive"))
      (node (ref "R16") (pin "1") (pinfunction "1_1") (pintype "passive"))
      (node (ref "R18") (pin "1") (pinfunction "1_1") (pintype "passive"))
      (node (ref "R20") (pin "1") (pinfunction "1_1") (pintype "passive"))
      (node (ref "R22") (pin "1") (pinfunction "1_1") (pintype "passive"))
      (node (ref "R24") (pin "1") (pinfunction "1_1") (pintype "passive"))
      (node (ref "R26") (pin "1") (pinfunction "1_1") (pintype "passive"))
      (node (ref "R28") (pin "1") (pinfunction "1_1") (pintype "passive"))
      (node (ref "R30") (pin "1") (pinfunction "1_1") (pintype "passive"))
      (node (ref "R32") (pin "1") (pinfunction "1_1") (pintype "passive"))
      (node (ref "R34") (pin "1") (pinfunction "1_1") (pintype "passive"))
      (node (ref "R36") (pin "1") (pinfunction "1_1") (pintype "passive"))
      (node (ref "R38") (pin "1") (pinfunction "1_1") (pintype "passive"))
      (node (ref "R4") (pin "1") (pinfunction "1_1") (pintype "passive"))
      (node (ref "R40") (pin "1") (pinfunction "1_1") (pintype "passive"))
      (node (ref "R42") (pin "1") (pinfunction "1_1") (pintype "passive"))
      (node (ref "R44") (pin "1") (pinfunction "1_1") (pintype "passive"))
      (node (ref "R46") (pin "1") (pinfunction "1_1") (pintype "passive"))
      (node (ref "R48") (pin "1") (pinfunction "1_1") (pintype "passive"))
      (node (ref "R50") (pin "1") (pinfunction "1_1") (pintype "passive"))
      (node (ref "R52") (pin "1") (pinfunction "1_1") (pintype "passive"))
      (node (ref "R54") (pin "1") (pinfunction "1_1") (pintype "passive"))
      (node (ref "R56") (pin "1") (pinfunction "1_1") (pintype "passive"))
      (node (ref "R58") (pin "1") (pinfunction "1_1") (pintype "passive"))
      (node (ref "R6") (pin "1") (pinfunction "1_1") (pintype "passive"))
      (node (ref "R60") (pin "1") (pinfunction "1_1") (pintype "passive"))
      (node (ref "R62") (pin "1") (pinfunction "1_1") (pintype "passive"))
      (node (ref "R8") (pin "1") (pinfunction "1_1") (pintype "passive"))
      (node (ref "U2") (pin "13") (pinfunction "VDDA/VREF+_13") (pintype "power_in"))
      (node (ref "U2") (pin "19") (pinfunction "VDD_19") (pintype "power_in"))
      (node (ref "U2") (pin "32") (pinfunction "VDD_32") (pintype "power_in"))
      (node (ref "U2") (pin "48") (pinfunction "VDD_48") (pintype "power_in"))
      (node (ref "U2") (pin "64") (pinfunction "VDD_64") (pintype "power_in"))
    )
    (net (code "2") (name "/32KHz_1") (class "Default")
      (node (ref "C16") (pin "2") (pinfunction "2_2") (pintype "passive"))
      (node (ref "U2") (pin "3") (pinfunction "PC14-OSC32_IN_3") (pintype "bidirectional"))
      (node (ref "Y2") (pin "2") (pinfunction "2_2") (pintype "passive"))
    )
    (net (code "3") (name "/32KHz_2") (class "Default")
      (node (ref "C17") (pin "2") (pinfunction "2_2") (pintype "passive"))
      (node (ref "U2") (pin "4") (pinfunction "PC15-OSC32_OUT_4") (pintype "bidirectional"))
      (node (ref "Y2") (pin "1") (pinfunction "1_1") (pintype "passive"))
    )
    (net (code "4") (name "/Boot0") (class "Default")
      (node (ref "J2") (pin "2") (pinfunction "2_2") (pintype "passive"))
      (node (ref "R2") (pin "2") (pinfunction "2_2") (pintype "passive"))
    )
    (net (code "5") (name "/NRST") (class "Default")
      (node (ref "C13") (pin "1") (pinfunction "1_1") (pintype "passive"))
      (node (ref "SW1") (pin "3") (pinfunction "3_3") (pintype "passive"))
      (node (ref "U2") (pin "7") (pinfunction "NRST_7") (pintype "bidirectional"))
    )
    (net (code "6") (name "/PA0") (class "Default")
      (node (ref "J4") (pin "9") (pinfunction "9_9") (pintype "passive"))
      (node (ref "R40") (pin "2") (pinfunction "2_2") (pintype "passive"))
      (node (ref "R41") (pin "1") (pinfunction "1_1") (pintype "passive"))
      (node (ref "U2") (pin "14") (pinfunction "PA0-WKUP_14") (pintype "bidirectional"))
    )
    (net (code "7") (name "/PA1") (class "Default")
      (node (ref "J4") (pin "10") (pinfunction "10_10") (pintype "passive"))
      (node (ref "R42") (pin "2") (pinfunction "2_2") (pintype "passive"))
      (node (ref "R43") (pin "1") (pinfunction "1_1") (pintype "passive"))
      (node (ref "U2") (pin "15") (pinfunction "PA1_15") (pintype "bidirectional"))
    )
    (net (code "8") (name "/PA2") (class "Default")
      (node (ref "J3") (pin "10") (pinfunction "10_10") (pintype "passive"))
      (node (ref "R22") (pin "2") (pinfunction "2_2") (pintype "passive"))
      (node (ref "R23") (pin "1") (pinfunction "1_1") (pintype "passive"))
      (node (ref "U2") (pin "16") (pinfunction "PA2_16") (pintype "bidirectional"))
    )
    (net (code "9") (name "/PA3") (class "Default")
      (node (ref "J3") (pin "9") (pinfunction "9_9") (pintype "passive"))
      (node (ref "R20") (pin "2") (pinfunction "2_2") (pintype "passive"))
      (node (ref "R21") (pin "1") (pinfunction "1_1") (pintype "passive"))
      (node (ref "U2") (pin "17") (pinfunction "PA3_17") (pintype "bidirectional"))
    )
    (net (code "10") (name "/PA4") (class "Default")
      (node (ref "J3") (pin "8") (pinfunction "8_8") (pintype "passive"))
      (node (ref "R18") (pin "2") (pinfunction "2_2") (pintype "passive"))
      (node (ref "R19") (pin "1") (pinfunction "1_1") (pintype "passive"))
      (node (ref "U2") (pin "20") (pinfunction "PA4_20") (pintype "bidirectional"))
    )
    (net (code "11") (name "/PA5") (class "Default")
      (node (ref "J3") (pin "7") (pinfunction "7_7") (pintype "passive"))
      (node (ref "R16") (pin "2") (pinfunction "2_2") (pintype "passive"))
      (node (ref "R17") (pin "1") (pinfunction "1_1") (pintype "passive"))
      (node (ref "U2") (pin "21") (pinfunction "PA5_21") (pintype "bidirectional"))
    )
    (net (code "12") (name "/PA6") (class "Default")
      (node (ref "J3") (pin "6") (pinfunction "6_6") (pintype "passive"))
      (node (ref "R14") (pin "2") (pinfunction "2_2") (pintype "passive"))
      (node (ref "R15") (pin "1") (pinfunction "1_1") (pintype "passive"))
      (node (ref "U2") (pin "22") (pinfunction "PA6_22") (pintype "bidirectional"))
    )
    (net (code "13") (name "/PA7") (class "Default")
      (node (ref "J3") (pin "5") (pinfunction "5_5") (pintype "passive"))
      (node (ref "R12") (pin "2") (pinfunction "2_2") (pintype "passive"))
      (node (ref "R13") (pin "1") (pinfunction "1_1") (pintype "passive"))
      (node (ref "U2") (pin "23") (pinfunction "PA7_23") (pintype "bidirectional"))
    )
    (net (code "14") (name "/PA8") (class "Default")
      (node (ref "J5") (pin "5") (pinfunction "5_5") (pintype "passive"))
      (node (ref "R52") (pin "2") (pinfunction "2_2") (pintype "passive"))
      (node (ref "R53") (pin "1") (pinfunction "1_1") (pintype "passive"))
      (node (ref "U2") (pin "41") (pinfunction "PA8_41") (pintype "bidirectional"))
    )
    (net (code "15") (name "/PA9") (class "Default")
      (node (ref "J5") (pin "6") (pinfunction "6_6") (pintype "passive"))
      (node (ref "R54") (pin "2") (pinfunction "2_2") (pintype "passive"))
      (node (ref "R55") (pin "1") (pinfunction "1_1") (pintype "passive"))
      (node (ref "U2") (pin "42") (pinfunction "PA9_42") (pintype "bidirectional"))
    )
    (net (code "16") (name "/PA10") (class "Default")
      (node (ref "J5") (pin "7") (pinfunction "7_7") (pintype "passive"))
      (node (ref "R56") (pin "2") (pinfunction "2_2") (pintype "passive"))
      (node (ref "R57") (pin "1") (pinfunction "1_1") (pintype "passive"))
      (node (ref "U2") (pin "43") (pinfunction "PA10_43") (pintype "bidirectional"))
    )
    (net (code "17") (name "/PA11") (class "Default")
      (node (ref "J5") (pin "8") (pinfunction "8_8") (pintype "passive"))
      (node (ref "R58") (pin "2") (pinfunction "2_2") (pintype "passive"))
      (node (ref "R59") (pin "1") (pinfunction "1_1") (pintype "passive"))
      (node (ref "U2") (pin "44") (pinfunction "PA11_44") (pintype "bidirectional"))
    )
    (net (code "18") (name "/PA12") (class "Default")
      (node (ref "J5") (pin "9") (pinfunction "9_9") (pintype "passive"))
      (node (ref "R60") (pin "2") (pinfunction "2_2") (pintype "passive"))
      (node (ref "R61") (pin "1") (pinfunction "1_1") (pintype "passive"))
      (node (ref "U2") (pin "45") (pinfunction "PA12_45") (pintype "bidirectional"))
    )
    (net (code "19") (name "/PA13") (class "Default")
      (node (ref "J5") (pin "10") (pinfunction "10_10") (pintype "passive"))
      (node (ref "R62") (pin "2") (pinfunction "2_2") (pintype "passive"))
      (node (ref "R63") (pin "1") (pinfunction "1_1") (pintype "passive"))
      (node (ref "U2") (pin "50") (pinfunction "PA15_50") (pintype "bidirectional"))
    )
    (net (code "20") (name "/PB0") (class "Default")
      (node (ref "J3") (pin "4") (pinfunction "4_4") (pintype "passive"))
      (node (ref "R10") (pin "2") (pinfunction "2_2") (pintype "passive"))
      (node (ref "R11") (pin "1") (pinfunction "1_1") (pintype "passive"))
      (node (ref "U2") (pin "26") (pinfunction "PB0_26") (pintype "bidirectional"))
    )
    (net (code "21") (name "/PB1") (class "Default")
      (node (ref "J3") (pin "3") (pinfunction "3_3") (pintype "passive"))
      (node (ref "R8") (pin "2") (pinfunction "2_2") (pintype "passive"))
      (node (ref "R9") (pin "1") (pinfunction "1_1") (pintype "passive"))
      (node (ref "U2") (pin "27") (pinfunction "PB1_27") (pintype "bidirectional"))
    )
    (net (code "22") (name "/PB2") (class "Default")
      (node (ref "J3") (pin "2") (pinfunction "2_2") (pintype "passive"))
      (node (ref "R6") (pin "2") (pinfunction "2_2") (pintype "passive"))
      (node (ref "R7") (pin "1") (pinfunction "1_1") (pintype "passive"))
      (node (ref "U2") (pin "28") (pinfunction "PB2_28") (pintype "bidirectional"))
    )
    (net (code "23") (name "/PB4") (class "Default")
      (node (ref "J4") (pin "1") (pinfunction "1_1") (pintype "passive"))
      (node (ref "R24") (pin "2") (pinfunction "2_2") (pintype "passive"))
      (node (ref "R25") (pin "1") (pinfunction "1_1") (pintype "passive"))
      (node (ref "U2") (pin "56") (pinfunction "PB4_56") (pintype "bidirectional"))
    )
    (net (code "24") (name "/PB5") (class "Default")
      (node (ref "J4") (pin "2") (pinfunction "2_2") (pintype "passive"))
      (node (ref "R26") (pin "2") (pinfunction "2_2") (pintype "passive"))
      (node (ref "R27") (pin "1") (pinfunction "1_1") (pintype "passive"))
      (node (ref "U2") (pin "57") (pinfunction "PB5_57") (pintype "bidirectional"))
    )
    (net (code "25") (name "/PB6") (class "Default")
      (node (ref "J4") (pin "3") (pinfunction "3_3") (pintype "passive"))
      (node (ref "R28") (pin "2") (pinfunction "2_2") (pintype "passive"))
      (node (ref "R29") (pin "1") (pinfunction "1_1") (pintype "passive"))
      (node (ref "U2") (pin "58") (pinfunction "PB6_58") (pintype "bidirectional"))
    )
    (net (code "26") (name "/PB7") (class "Default")
      (node (ref "J4") (pin "4") (pinfunction "4_4") (pintype "passive"))
      (node (ref "R30") (pin "2") (pinfunction "2_2") (pintype "passive"))
      (node (ref "R31") (pin "1") (pinfunction "1_1") (pintype "passive"))
      (node (ref "U2") (pin "59") (pinfunction "PB7_59") (pintype "bidirectional"))
    )
    (net (code "27") (name "/PB8") (class "Default")
      (node (ref "J4") (pin "5") (pinfunction "5_5") (pintype "passive"))
      (node (ref "R32") (pin "2") (pinfunction "2_2") (pintype "passive"))
      (node (ref "R33") (pin "1") (pinfunction "1_1") (pintype "passive"))
      (node (ref "U2") (pin "61") (pinfunction "PB8_61") (pintype "bidirectional"))
    )
    (net (code "28") (name "/PB9") (class "Default")
      (node (ref "J4") (pin "6") (pinfunction "6_6") (pintype "passive"))
      (node (ref "R34") (pin "2") (pinfunction "2_2") (pintype "passive"))
      (node (ref "R35") (pin "1") (pinfunction "1_1") (pintype "passive"))
      (node (ref "U2") (pin "62") (pinfunction "PB9_62") (pintype "bidirectional"))
    )
    (net (code "29") (name "/PB10") (class "Default")
      (node (ref "J3") (pin "1") (pinfunction "1_1") (pintype "passive"))
      (node (ref "R4") (pin "2") (pinfunction "2_2") (pintype "passive"))
      (node (ref "R5") (pin "1") (pinfunction "1_1") (pintype "passive"))
      (node (ref "U2") (pin "29") (pinfunction "PB10_29") (pintype "bidirectional"))
    )
    (net (code "30") (name "/PB11") (class "Default")
      (node (ref "J5") (pin "1") (pinfunction "1_1") (pintype "passive"))
      (node (ref "R44") (pin "2") (pinfunction "2_2") (pintype "passive"))
      (node (ref "R45") (pin "1") (pinfunction "1_1") (pintype "passive"))
      (node (ref "U2") (pin "33") (pinfunction "PB12_33") (pintype "bidirectional"))
    )
    (net (code "31") (name "/PB12") (class "Default")
      (node (ref "J5") (pin "2") (pinfunction "2_2") (pintype "passive"))
      (node (ref "R46") (pin "2") (pinfunction "2_2") (pintype "passive"))
      (node (ref "R47") (pin "1") (pinfunction "1_1") (pintype "passive"))
      (node (ref "U2") (pin "34") (pinfunction "PB13_34") (pintype "bidirectional"))
    )
    (net (code "32") (name "/PB13") (class "Default")
      (node (ref "J5") (pin "3") (pinfunction "3_3") (pintype "passive"))
      (node (ref "R48") (pin "2") (pinfunction "2_2") (pintype "passive"))
      (node (ref "R49") (pin "1") (pinfunction "1_1") (pintype "passive"))
      (node (ref "U2") (pin "35") (pinfunction "PB14_35") (pintype "bidirectional"))
    )
    (net (code "33") (name "/PB14") (class "Default")
      (node (ref "J5") (pin "4") (pinfunction "4_4") (pintype "passive"))
      (node (ref "R50") (pin "2") (pinfunction "2_2") (pintype "passive"))
      (node (ref "R51") (pin "1") (pinfunction "1_1") (pintype "passive"))
      (node (ref "U2") (pin "36") (pinfunction "PB15_36") (pintype "bidirectional"))
    )
    (net (code "34") (name "/PC0") (class "Default")
      (node (ref "J4") (pin "7") (pinfunction "7_7") (pintype "passive"))
      (node (ref "R36") (pin "2") (pinfunction "2_2") (pintype "passive"))
      (node (ref "R37") (pin "1") (pinfunction "1_1") (pintype "passive"))
      (node (ref "U2") (pin "8") (pinfunction "PC0_8") (pintype "bidirectional"))
    )
    (net (code "35") (name "/PC1") (class "Default")
      (node (ref "J4") (pin "8") (pinfunction "8_8") (pintype "passive"))
      (node (ref "R38") (pin "2") (pinfunction "2_2") (pintype "passive"))
      (node (ref "R39") (pin "1") (pinfunction "1_1") (pintype "passive"))
      (node (ref "U2") (pin "9") (pinfunction "PC1_9") (pintype "bidirectional"))
    )
    (net (code "36") (name "/SWCLK") (class "Default")
      (node (ref "P1") (pin "3") (pinfunction "3_3") (pintype "passive"))
      (node (ref "U2") (pin "49") (pinfunction "PA14_49") (pintype "bidirectional"))
    )
    (net (code "37") (name "/SWDIO") (class "Default")
      (node (ref "P1") (pin "2") (pinfunction "2_2") (pintype "passive"))
      (node (ref "U2") (pin "46") (pinfunction "PA13_46") (pintype "bidirectional"))
    )
    (net (code "38") (name "/in{slash}out") (class "Default")
      (node (ref "C14") (pin "2") (pinfunction "2_2") (pintype "passive"))
      (node (ref "R1") (pin "2") (pinfunction "2_2") (pintype "passive"))
      (node (ref "Y1") (pin "1") (pinfunction "IN/OUT_1") (pintype "bidirectional"))
    )
    (net (code "39") (name "/out{slash}in") (class "Default")
      (node (ref "C15") (pin "2") (pinfunction "2_2") (pintype "passive"))
      (node (ref "U2") (pin "5") (pinfunction "PH0-OSC_IN_5") (pintype "bidirectional"))
      (node (ref "Y1") (pin "3") (pinfunction "OUT/IN_3") (pintype "bidirectional"))
    )
    (net (code "40") (name "GND") (class "Default")
      (node (ref "C10") (pin "2") (pinfunction "2_2") (pintype "passive"))
      (node (ref "C11") (pin "2") (pinfunction "2_2") (pintype "passive"))
      (node (ref "C12") (pin "2") (pinfunction "2_2") (pintype "passive"))
      (node (ref "C13") (pin "2") (pinfunction "2_2") (pintype "passive"))
      (node (ref "C14") (pin "1") (pinfunction "1_1") (pintype "passive"))
      (node (ref "C15") (pin "1") (pinfunction "1_1") (pintype "passive"))
      (node (ref "C16") (pin "1") (pinfunction "1_1") (pintype "passive"))
      (node (ref "C17") (pin "1") (pinfunction "1_1") (pintype "passive"))
      (node (ref "C4") (pin "2") (pinfunction "2_2") (pintype "passive"))
      (node (ref "C5") (pin "2") (pinfunction "2_2") (pintype "passive"))
      (node (ref "C6") (pin "2") (pinfunction "2_2") (pintype "passive"))
      (node (ref "C7") (pin "2") (pinfunction "2_2") (pintype "passive"))
      (node (ref "C8") (pin "2") (pinfunction "2_2") (pintype "passive"))
      (node (ref "C9") (pin "2") (pinfunction "2_2") (pintype "passive"))
      (node (ref "J2") (pin "3") (pinfunction "3_3") (pintype "passive"))
      (node (ref "P1") (pin "4") (pinfunction "4_4") (pintype "passive"))
      (node (ref "R11") (pin "2") (pinfunction "2_2") (pintype "passive"))
      (node (ref "R13") (pin "2") (pinfunction "2_2") (pintype "passive"))
      (node (ref "R15") (pin "2") (pinfunction "2_2") (pintype "passive"))
      (node (ref "R17") (pin "2") (pinfunction "2_2") (pintype "passive"))
      (node (ref "R19") (pin "2") (pinfunction "2_2") (pintype "passive"))
      (node (ref "R21") (pin "2") (pinfunction "2_2") (pintype "passive"))
      (node (ref "R23") (pin "2") (pinfunction "2_2") (pintype "passive"))
      (node (ref "R25") (pin "2") (pinfunction "2_2") (pintype "passive"))
      (node (ref "R27") (pin "2") (pinfunction "2_2") (pintype "passive"))
      (node (ref "R29") (pin "2") (pinfunction "2_2") (pintype "passive"))
      (node (ref "R31") (pin "2") (pinfunction "2_2") (pintype "passive"))
      (node (ref "R33") (pin "2") (pinfunction "2_2") (pintype "passive"))
      (node (ref "R35") (pin "2") (pinfunction "2_2") (pintype "passive"))
      (node (ref "R37") (pin "2") (pinfunction "2_2") (pintype "passive"))
      (node (ref "R39") (pin "2") (pinfunction "2_2") (pintype "passive"))
      (node (ref "R41") (pin "2") (pinfunction "2_2") (pintype "passive"))
      (node (ref "R43") (pin "2") (pinfunction "2_2") (pintype "passive"))
      (node (ref "R45") (pin "2") (pinfunction "2_2") (pintype "passive"))
      (node (ref "R47") (pin "2") (pinfunction "2_2") (pintype "passive"))
      (node (ref "R49") (pin "2") (pinfunction "2_2") (pintype "passive"))
      (node (ref "R5") (pin "2") (pinfunction "2_2") (pintype "passive"))
      (node (ref "R51") (pin "2") (pinfunction "2_2") (pintype "passive"))
      (node (ref "R53") (pin "2") (pinfunction "2_2") (pintype "passive"))
      (node (ref "R55") (pin "2") (pinfunction "2_2") (pintype "passive"))
      (node (ref "R57") (pin "2") (pinfunction "2_2") (pintype "passive"))
      (node (ref "R59") (pin "2") (pinfunction "2_2") (pintype "passive"))
      (node (ref "R61") (pin "2") (pinfunction "2_2") (pintype "passive"))
      (node (ref "R63") (pin "2") (pinfunction "2_2") (pintype "passive"))
      (node (ref "R7") (pin "2") (pinfunction "2_2") (pintype "passive"))
      (node (ref "R9") (pin "2") (pinfunction "2_2") (pintype "passive"))
      (node (ref "SW1") (pin "2") (pinfunction "2_2") (pintype "passive"))
      (node (ref "U2") (pin "12") (pinfunction "VSSA/VREF-_12") (pintype "power_in"))
      (node (ref "U2") (pin "18") (pinfunction "VSS_18") (pintype "power_in"))
      (node (ref "U2") (pin "31") (pinfunction "VSS_31") (pintype "power_in"))
      (node (ref "U2") (pin "47") (pinfunction "VSS_47") (pintype "power_in"))
      (node (ref "U2") (pin "63") (pinfunction "VSS_63") (pintype "power_in"))
      (node (ref "Y1") (pin "2") (pinfunction "GND_2") (pintype "power_in"))
      (node (ref "Y1") (pin "4") (pinfunction "GND_4") (pintype "power_in"))
    )
    (net (code "41") (name "Net-(U2A-BOOT0)") (class "Default")
      (node (ref "R2") (pin "1") (pinfunction "1_1") (pintype "passive"))
      (node (ref "U2") (pin "60") (pinfunction "BOOT0_60") (pintype "input"))
    )
    (net (code "42") (name "Net-(U2A-PH1-OSC_OUT)") (class "Default")
      (node (ref "R1") (pin "1") (pinfunction "1_1") (pintype "passive"))
      (node (ref "U2") (pin "6") (pinfunction "PH1-OSC_OUT_6") (pintype "bidirectional"))
    )
    (net (code "43") (name "unconnected-(SW1-Pad1)") (class "Default")
      (node (ref "SW1") (pin "1") (pinfunction "1_1") (pintype "passive"))
    )
    (net (code "44") (name "unconnected-(SW1-Pad4)") (class "Default")
      (node (ref "SW1") (pin "4") (pinfunction "4_4") (pintype "passive"))
    )
    (net (code "45") (name "unconnected-(U2A-PB3-Pad55)") (class "Default")
      (node (ref "U2") (pin "55") (pinfunction "PB3_55") (pintype "bidirectional"))
    )
    (net (code "46") (name "unconnected-(U2A-PC2-Pad10)") (class "Default")
      (node (ref "U2") (pin "10") (pinfunction "PC2_10") (pintype "bidirectional"))
    )
    (net (code "47") (name "unconnected-(U2A-PC3-Pad11)") (class "Default")
      (node (ref "U2") (pin "11") (pinfunction "PC3_11") (pintype "bidirectional"))
    )
    (net (code "48") (name "unconnected-(U2A-PC4-Pad24)") (class "Default")
      (node (ref "U2") (pin "24") (pinfunction "PC4_24") (pintype "bidirectional"))
    )
    (net (code "49") (name "unconnected-(U2A-PC5-Pad25)") (class "Default")
      (node (ref "U2") (pin "25") (pinfunction "PC5_25") (pintype "bidirectional"))
    )
    (net (code "50") (name "unconnected-(U2A-PC6-Pad37)") (class "Default")
      (node (ref "U2") (pin "37") (pinfunction "PC6_37") (pintype "bidirectional"))
    )
    (net (code "51") (name "unconnected-(U2A-PC7-Pad38)") (class "Default")
      (node (ref "U2") (pin "38") (pinfunction "PC7_38") (pintype "bidirectional"))
    )
    (net (code "52") (name "unconnected-(U2A-PC8-Pad39)") (class "Default")
      (node (ref "U2") (pin "39") (pinfunction "PC8_39") (pintype "bidirectional"))
    )
    (net (code "53") (name "unconnected-(U2A-PC9-Pad40)") (class "Default")
      (node (ref "U2") (pin "40") (pinfunction "PC9_40") (pintype "bidirectional"))
    )
    (net (code "54") (name "unconnected-(U2A-PC10-Pad51)") (class "Default")
      (node (ref "U2") (pin "51") (pinfunction "PC10_51") (pintype "bidirectional"))
    )
    (net (code "55") (name "unconnected-(U2A-PC11-Pad52)") (class "Default")
      (node (ref "U2") (pin "52") (pinfunction "PC11_52") (pintype "bidirectional"))
    )
    (net (code "56") (name "unconnected-(U2A-PC12-Pad53)") (class "Default")
      (node (ref "U2") (pin "53") (pinfunction "PC12_53") (pintype "bidirectional"))
    )
    (net (code "57") (name "unconnected-(U2A-PC13-ANTI_TAMP-Pad2)") (class "Default")
      (node (ref "U2") (pin "2") (pinfunction "PC13-ANTI_TAMP_2") (pintype "bidirectional"))
    )
    (net (code "58") (name "unconnected-(U2A-PD2-Pad54)") (class "Default")
      (node (ref "U2") (pin "54") (pinfunction "PD2_54") (pintype "bidirectional"))
    )
    (net (code "59") (name "unconnected-(U2A-VCAP1-Pad30)") (class "Default")
      (node (ref "U2") (pin "30") (pinfunction "VCAP1_30") (pintype "power_in"))
    )
    (net (code "60") (name "unconnected-(U2B-VBAT-Pad1)") (class "Default")
      (node (ref "U2") (pin "1") (pinfunction "VBAT_1") (pintype "power_in"))
    )
  )
)
